# K-Diag_small-_single_small.net
KiCad netlist of a schematic drawn in EAGLE
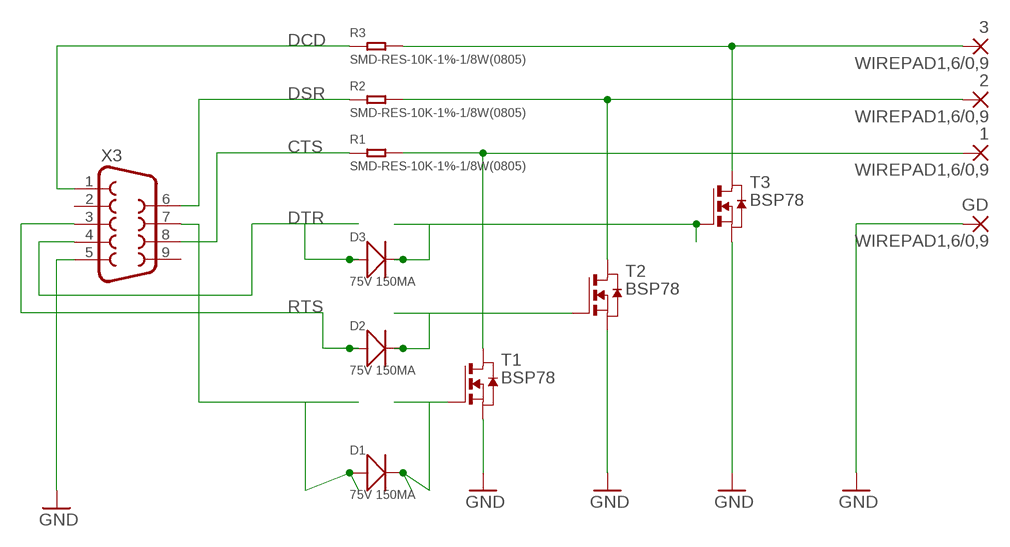
[diagram p0: schematic, sheet 1]

(export (version "E")
  (design (tool "Eeschema 10.0.6"))
  (components
    (comp (ref "1")
      (value "WIREPAD1,6/0,9")
      (footprint "eagle-import:1,6_0,9")
      (libsource (lib "eagle-import") (part "WIREPAD1,6/0,9"))
    )
    (comp (ref "2")
      (value "WIREPAD1,6/0,9")
      (footprint "eagle-import:1,6_0,9")
      (libsource (lib "eagle-import") (part "WIREPAD1,6/0,9"))
    )
    (comp (ref "3")
      (value "WIREPAD1,6/0,9")
      (footprint "eagle-import:1,6_0,9")
      (libsource (lib "eagle-import") (part "WIREPAD1,6/0,9"))
    )
    (comp (ref "D1")
      (value "75V 150MA")
      (footprint "eagle-import:LED-1206")
      (fields (field (name "MPN") "CD1206-S01575"))
      (libsource (lib "eagle-import") (part "SMD-DIODE-SWITCHING-75V-150MA(D1206)"))
    )
    (comp (ref "D2")
      (value "75V 150MA")
      (footprint "eagle-import:LED-1206")
      (fields (field (name "MPN") "CD1206-S01575"))
      (libsource (lib "eagle-import") (part "SMD-DIODE-SWITCHING-75V-150MA(D1206)"))
    )
    (comp (ref "D3")
      (value "75V 150MA")
      (footprint "eagle-import:LED-1206")
      (fields (field (name "MPN") "CD1206-S01575"))
      (libsource (lib "eagle-import") (part "SMD-DIODE-SWITCHING-75V-150MA(D1206)"))
    )
    (comp (ref "GD")
      (value "WIREPAD1,6/0,9")
      (footprint "eagle-import:1,6_0,9")
      (libsource (lib "eagle-import") (part "WIREPAD1,6/0,9"))
    )
    (comp (ref "R1")
      (value "SMD-RES-10K-1%-1/8W(0805)")
      (footprint "eagle-import:R0805")
      (fields (field (name "MPN") "RC0805FR-0710KL"))
      (libsource (lib "eagle-import") (part "SMD-RES-10K-1%-1/8W(0805)"))
    )
    (comp (ref "R2")
      (value "SMD-RES-10K-1%-1/8W(0805)")
      (footprint "eagle-import:R0805")
      (fields (field (name "MPN") "RC0805FR-0710KL"))
      (libsource (lib "eagle-import") (part "SMD-RES-10K-1%-1/8W(0805)"))
    )
    (comp (ref "R3")
      (value "SMD-RES-10K-1%-1/8W(0805)")
      (footprint "eagle-import:R0805")
      (fields (field (name "MPN") "RC0805FR-0710KL"))
      (libsource (lib "eagle-import") (part "SMD-RES-10K-1%-1/8W(0805)"))
    )
    (comp (ref "T1")
      (value "BSP78")
      (footprint "eagle-import:SOT223")
      (libsource (lib "eagle-import") (part "NMOSSOT223"))
    )
    (comp (ref "T2")
      (value "BSP78")
      (footprint "eagle-import:SOT223")
      (libsource (lib "eagle-import") (part "NMOSSOT223"))
    )
    (comp (ref "T3")
      (value "BSP78")
      (footprint "eagle-import:SOT223")
      (libsource (lib "eagle-import") (part "NMOSSOT223"))
    )
    (comp (ref "X3")
      (value "F09D")
      (footprint "eagle-import:F09D")
      (libsource (lib "eagle-import") (part "F09D"))
    )
  )
  (nets
    (net (code "1") (name "/CTS") (class "Default")
      (node (ref "R1") (pin "1") (pinfunction "1_1") (pintype "passive"))
      (node (ref "X3") (pin "8") (pinfunction "8_8") (pintype "passive"))
    )
    (net (code "2") (name "/DCD") (class "Default")
      (node (ref "R3") (pin "1") (pinfunction "1_1") (pintype "passive"))
      (node (ref "X3") (pin "1") (pinfunction "1_1") (pintype "passive"))
    )
    (net (code "3") (name "/DSR") (class "Default")
      (node (ref "R2") (pin "1") (pinfunction "1_1") (pintype "passive"))
      (node (ref "X3") (pin "6") (pinfunction "6_6") (pintype "passive"))
    )
    (net (code "4") (name "/DTR") (class "Default")
      (node (ref "D3") (pin "+") (pinfunction "+_+") (pintype "passive"))
      (node (ref "X3") (pin "4") (pinfunction "4_4") (pintype "passive"))
    )
    (net (code "5") (name "/RTS") (class "Default")
      (node (ref "D2") (pin "+") (pinfunction "+_+") (pintype "passive"))
      (node (ref "X3") (pin "3") (pinfunction "3_3") (pintype "passive"))
    )
    (net (code "6") (name "GND") (class "Default")
      (node (ref "GD") (pin "1") (pinfunction "P_1") (pintype "passive"))
      (node (ref "T1") (pin "3") (pinfunction "S_3") (pintype "passive"))
      (node (ref "T2") (pin "3") (pinfunction "S_3") (pintype "passive"))
      (node (ref "T3") (pin "3") (pinfunction "S_3") (pintype "passive"))
      (node (ref "X3") (pin "5") (pinfunction "5_5") (pintype "passive"))
    )
    (net (code "7") (name "Net-(1-P)") (class "Default")
      (node (ref "1") (pin "1") (pinfunction "P_1") (pintype "passive"))
      (node (ref "R1") (pin "2") (pinfunction "2_2") (pintype "passive"))
      (node (ref "T1") (pin "2") (pinfunction "D_2") (pintype "passive"))
      (node (ref "T1") (pin "4") (pinfunction "D_4") (pintype "passive"))
    )
    (net (code "8") (name "Net-(2-P)") (class "Default")
      (node (ref "2") (pin "1") (pinfunction "P_1") (pintype "passive"))
      (node (ref "R2") (pin "2") (pinfunction "2_2") (pintype "passive"))
      (node (ref "T2") (pin "2") (pinfunction "D_2") (pintype "passive"))
      (node (ref "T2") (pin "4") (pinfunction "D_4") (pintype "passive"))
    )
    (net (code "9") (name "Net-(3-P)") (class "Default")
      (node (ref "3") (pin "1") (pinfunction "P_1") (pintype "passive"))
      (node (ref "R3") (pin "2") (pinfunction "2_2") (pintype "passive"))
      (node (ref "T3") (pin "2") (pinfunction "D_2") (pintype "passive"))
      (node (ref "T3") (pin "4") (pinfunction "D_4") (pintype "passive"))
    )
    (net (code "10") (name "Net-(D1-Pad+)") (class "Default")
      (node (ref "D1") (pin "+") (pinfunction "+_+") (pintype "passive"))
      (node (ref "X3") (pin "7") (pinfunction "7_7") (pintype "passive"))
    )
    (net (code "11") (name "Net-(T1-G)") (class "Default")
      (node (ref "D1") (pin "-") (pinfunction "-_-") (pintype "passive"))
      (node (ref "T1") (pin "1") (pinfunction "G_1") (pintype "passive"))
    )
    (net (code "12") (name "Net-(T2-G)") (class "Default")
      (node (ref "D2") (pin "-") (pinfunction "-_-") (pintype "passive"))
      (node (ref "T2") (pin "1") (pinfunction "G_1") (pintype "passive"))
    )
    (net (code "13") (name "Net-(T3-G)") (class "Default")
      (node (ref "D3") (pin "-") (pinfunction "-_-") (pintype "passive"))
      (node (ref "T3") (pin "1") (pinfunction "G_1") (pintype "passive"))
    )
    (net (code "14") (name "unconnected-(X3-Pad2)") (class "Default")
      (node (ref "X3") (pin "2") (pinfunction "2_2") (pintype "passive"))
    )
    (net (code "15") (name "unconnected-(X3-Pad9)") (class "Default")
      (node (ref "X3") (pin "9") (pinfunction "9_9") (pintype "passive"))
    )
  )
)
